# CH3-Input.net
KiCad netlist of a schematic drawn in Altium Designer
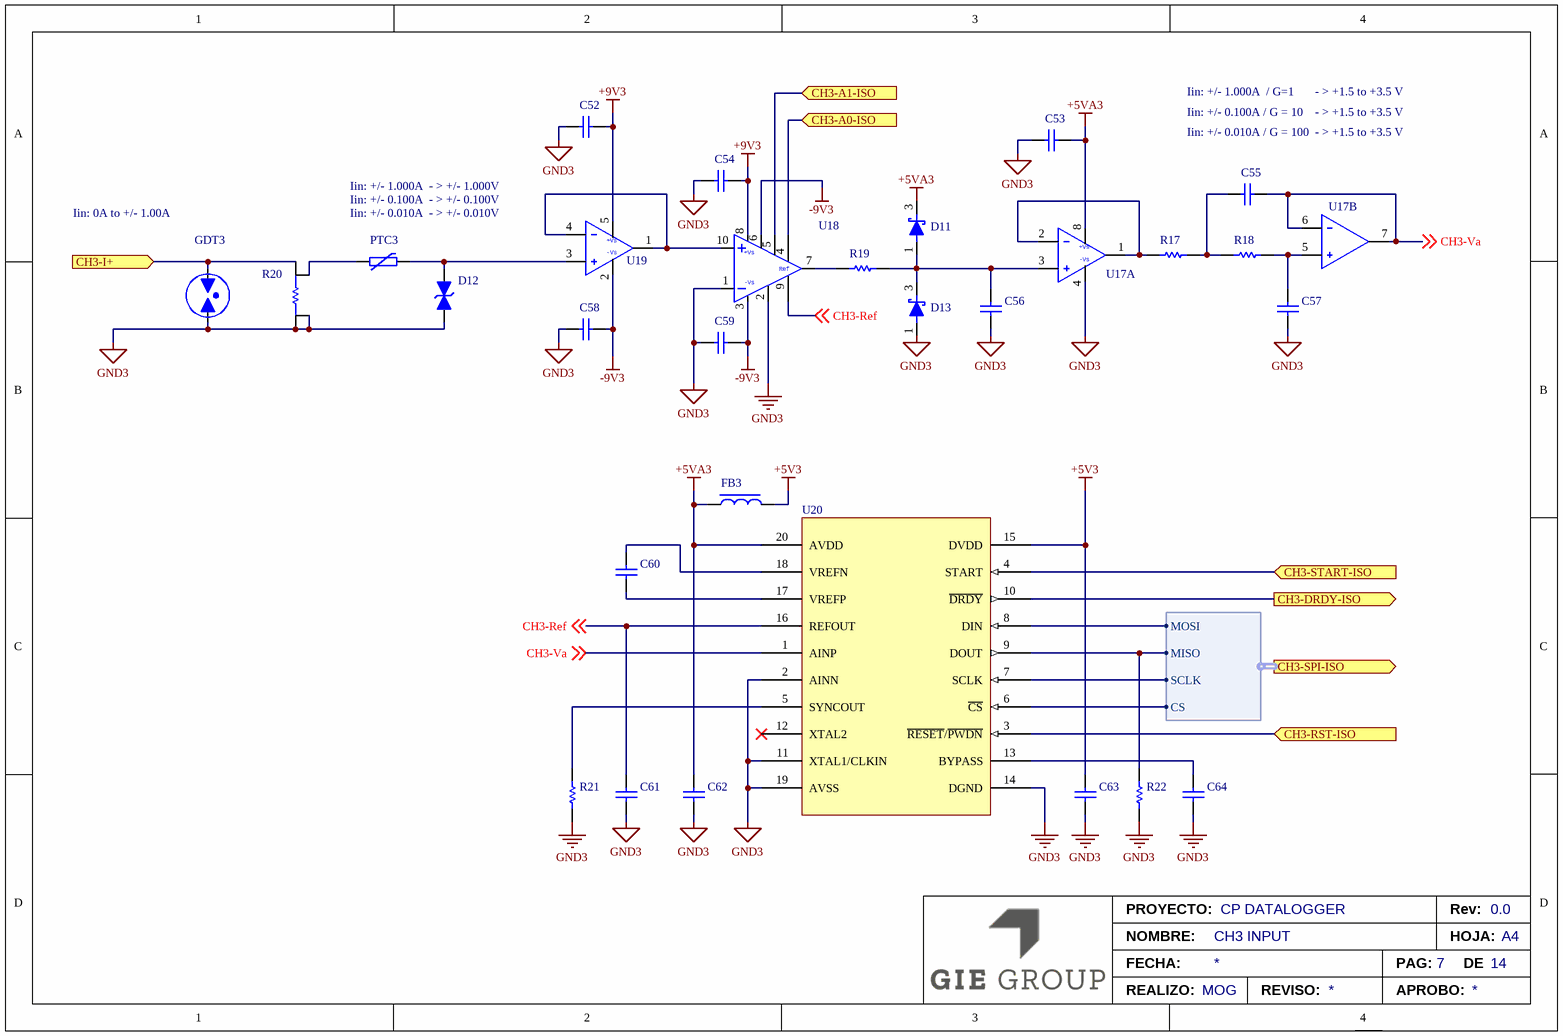
[diagram p0: CH3-Input.SchDoc]

(export (version "E")
  (design (tool "Eeschema 10.0.6"))
  (components
    (comp (ref "C52")
      (value "C0603C104K5RACAUTO")
      (footprint "CAP-0603")
      (description "CAP CER 0.1uF 50V X7R 0603")
      (fields (field (name "MANUFACTURER") "Kemet") (field (name "TOLERANCE") "10%"))
      (libsource (lib "Kemet") (part "C0603C104K5RACAUTO"))
    )
    (comp (ref "C53")
      (value "C0603C104K5RACAUTO")
      (footprint "CAP-0603")
      (description "CAP CER 0.1uF 50V X7R 0603")
      (fields (field (name "MANUFACTURER") "Kemet") (field (name "TOLERANCE") "10%"))
      (libsource (lib "Kemet") (part "C0603C104K5RACAUTO"))
    )
    (comp (ref "C54")
      (value "C0603C104K5RACAUTO")
      (footprint "CAP-0603")
      (description "CAP CER 0.1uF 50V X7R 0603")
      (fields (field (name "MANUFACTURER") "Kemet") (field (name "TOLERANCE") "10%"))
      (libsource (lib "Kemet") (part "C0603C104K5RACAUTO"))
    )
    (comp (ref "C55")
      (value "C0603C162J5GAC7867")
      (footprint "CAP-0603")
      (description "CAP CER 1600´pF 50V C0G 0603")
      (fields (field (name "MANUFACTURER") "Kemet") (field (name "TOLERANCE") "5%"))
      (libsource (lib "Kemet") (part "C0603C162J5GAC7867"))
    )
    (comp (ref "C56")
      (value "C0603C162J5GAC7867")
      (footprint "CAP-0603")
      (description "CAP CER 1600´pF 50V C0G 0603")
      (fields (field (name "MANUFACTURER") "Kemet") (field (name "TOLERANCE") "5%"))
      (libsource (lib "Kemet") (part "C0603C162J5GAC7867"))
    )
    (comp (ref "C57")
      (value "C0603C161J1GAC7867")
      (footprint "CAP-0603")
      (description "CAP CER 160 pF 100V C0G 0603")
      (fields (field (name "MANUFACTURER") "Kemet") (field (name "TOLERANCE") "5%"))
      (libsource (lib "Kemet") (part "C0603C161J1GAC7867"))
    )
    (comp (ref "C58")
      (value "C0603C104K5RACAUTO")
      (footprint "CAP-0603")
      (description "CAP CER 0.1uF 50V X7R 0603")
      (fields (field (name "MANUFACTURER") "Kemet") (field (name "TOLERANCE") "10%"))
      (libsource (lib "Kemet") (part "C0603C104K5RACAUTO"))
    )
    (comp (ref "C59")
      (value "C0603C104K5RACAUTO")
      (footprint "CAP-0603")
      (description "CAP CER 0.1uF 50V X7R 0603")
      (fields (field (name "MANUFACTURER") "Kemet") (field (name "TOLERANCE") "10%"))
      (libsource (lib "Kemet") (part "C0603C104K5RACAUTO"))
    )
    (comp (ref "C60")
      (value "C0603C105M3RAC7867")
      (footprint "CAP-0603")
      (description "CAP CER 1uF 25V X7R 0603")
      (fields (field (name "MANUFACTURER") "Kemet") (field (name "TOLERANCE") "20%"))
      (libsource (lib "Kemet") (part "C0603C105M3RAC7867"))
    )
    (comp (ref "C61")
      (value "C0603C105M3RAC7867")
      (footprint "CAP-0603")
      (description "CAP CER 1uF 25V X7R 0603")
      (fields (field (name "MANUFACTURER") "Kemet") (field (name "TOLERANCE") "20%"))
      (libsource (lib "Kemet") (part "C0603C105M3RAC7867"))
    )
    (comp (ref "C62")
      (value "C0603C105M3RAC7867")
      (footprint "CAP-0603")
      (description "CAP CER 1uF 25V X7R 0603")
      (fields (field (name "MANUFACTURER") "Kemet") (field (name "TOLERANCE") "20%"))
      (libsource (lib "Kemet") (part "C0603C105M3RAC7867"))
    )
    (comp (ref "C63")
      (value "C0603C105M3RAC7867")
      (footprint "CAP-0603")
      (description "CAP CER 1uF 25V X7R 0603")
      (fields (field (name "MANUFACTURER") "Kemet") (field (name "TOLERANCE") "20%"))
      (libsource (lib "Kemet") (part "C0603C105M3RAC7867"))
    )
    (comp (ref "C64")
      (value "C0603C105M3RAC7867")
      (footprint "CAP-0603")
      (description "CAP CER 1uF 25V X7R 0603")
      (fields (field (name "MANUFACTURER") "Kemet") (field (name "TOLERANCE") "20%"))
      (libsource (lib "Kemet") (part "C0603C105M3RAC7867"))
    )
    (comp (ref "D11")
      (value "NSVBAT54WT1G")
      (footprint "SOT-323-3")
      (description "Schottky Diode 30V 200mA SOT323")
      (fields (field (name "MANUFACTURER") "OnSemiconductor"))
      (libsource (lib "OnSemiconductors") (part "NSVBAT54WT1G"))
    )
    (comp (ref "D12")
      (value "~")
      (footprint "DIODE-0603")
      (description "TVS Diode 1.5kW 130V 5% Bi-Directional")
      (fields (field (name "MANUFACTURER") "Diodes Inc"))
      (libsource (lib "DidesInc") (part "D3V3L1B2LP3-7"))
    )
    (comp (ref "D13")
      (value "~")
      (footprint "SOT-323-3")
      (description "Schottky Diode 30V 200mA SOT323")
      (fields (field (name "MANUFACTURER") "OnSemiconductor"))
      (libsource (lib "OnSemiconductors") (part "NSVBAT54WT1G"))
    )
    (comp (ref "FB3")
      (value "Z0603C121GPWZT")
      (footprint "IND-0603")
      (description "Ferrite Bead 120Ohms 900mA 25% DCR=130m")
      (fields (field (name "MANUFACTURER") "Kemet"))
      (libsource (lib "Kemet") (part "Z0603C121GPWZT"))
    )
    (comp (ref "GDT3")
      (value "~")
      (footprint "LITTLELFUSE-CG5XXXLTR")
      (description "Gas Discharge Tube 145V")
      (fields (field (name "MANUFACTURER") "Littelfuse"))
      (libsource (lib "Littlelfuse") (part "CG5145LTR"))
    )
    (comp (ref "PTC3")
      (value "~")
      (footprint "LITTLELFUSE-72R020X")
      (description "PTC Polyfuse Radial 72V 0.2A")
      (fields (field (name "MANUFACTURER") "Littlelfuse"))
      (libsource (lib "Littlelfuse") (part "72R020XPR"))
    )
    (comp (ref "R17")
      (value "RC0603FR-07113KL")
      (footprint "RES-0603")
      (description "RES SMD 113K OHM 1% 1/10W 0603")
      (fields (field (name "TOLERANCE") "1%") (field (name "MANUFACTURER") "Yageo"))
      (libsource (lib "Yageo") (part "RC0603FR-07113KL"))
    )
    (comp (ref "R18")
      (value "RC0603FR-07887KL")
      (footprint "RES-0603")
      (description "RES SMD 887K OHM 1% 1/10W 0603")
      (fields (field (name "TOLERANCE") "1%") (field (name "MANUFACTURER") "Yageo"))
      (libsource (lib "Yageo") (part "RC0603FR-07887KL"))
    )
    (comp (ref "R19")
      (value "RC0603FR-07100KL")
      (footprint "RES-0603")
      (description "RES SMD 100K OHM 1% 1/10W 0603")
      (fields (field (name "TOLERANCE") "1%") (field (name "MANUFACTURER") "Yageo"))
      (libsource (lib "Yageo") (part "RC0603FR-07100KL"))
    )
    (comp (ref "R20")
      (value "Y16061R00000B9W")
      (footprint "RES-2512 WIDE")
      (description "RES SMD 1 OHM 1W 2516 WIDE")
      (fields (field (name "MANUFACTURER") "Vishay"))
      (libsource (lib "Vishay") (part "Y16061R00000B9W"))
    )
    (comp (ref "R21")
      (value "RC0603FR-071ML")
      (footprint "RES-0603")
      (description "RES SMD 1M OHM 1% 1/10W 0603")
      (fields (field (name "TOLERANCE") "1%") (field (name "MANUFACTURER") "Yageo"))
      (libsource (lib "Yageo") (part "RC0603FR-071ML"))
    )
    (comp (ref "R22")
      (value "RC0603FR-071ML")
      (footprint "RES-0603")
      (description "RES SMD 1M OHM 1% 1/10W 0603")
      (fields (field (name "TOLERANCE") "1%") (field (name "MANUFACTURER") "Yageo"))
      (libsource (lib "Yageo") (part "RC0603FR-071ML"))
    )
    (comp (ref "U17")
      (value "~")
      (footprint "MSOP8")
      (description "Dual  Precision Amplifier Micro Power Auto Zero")
      (fields (field (name "MANUFACTURER") "Analog Devices"))
      (libsource (lib "AnalogDevices") (part "ADA4051-2ARMZ"))
    )
    (comp (ref "U18")
      (value "AD8253ARMZ")
      (footprint "MSOP10")
      (description "Instrumentation Amplifiers High Speed Programmable High Gain In-Amp")
      (fields (field (name "MANUFACTURER") "Analog Devices Inc"))
      (libsource (lib "AnalogDevices") (part "AD8253ARMZ"))
    )
    (comp (ref "U19")
      (value "~")
      (footprint "SOT23-5")
      (description "16V Auto-Zero CMOS Amplifier")
      (fields (field (name "MANUFACTURER") "Analog Devices"))
      (libsource (lib "AnalogDevices") (part "AD8638ARJZ"))
    )
    (comp (ref "U20")
      (value "~")
      (footprint "TSSOP20")
      (description "Analog to Digital Converter 14.4kSPS 24-Bit")
      (fields (field (name "MANUFACTURER") "Texas Instruments"))
      (libsource (lib "TexasInstruments") (part "ADS1259BIPW"))
    )
  )
  (nets
    (net (code "2") (name "+5V3") (class "Default")
      (node (ref "C63") (pin "2") (pinfunction "2_2") (pintype "passive"))
      (node (ref "FB3") (pin "2") (pinfunction "2_2") (pintype "passive"))
      (node (ref "U20") (pin "15") (pinfunction "DVDD_15") (pintype "power_in"))
    )
    (net (code "3") (name "+5VA3") (class "Default")
      (node (ref "C53") (pin "2") (pinfunction "2_2") (pintype "passive"))
      (node (ref "C62") (pin "2") (pinfunction "2_2") (pintype "passive"))
      (node (ref "D11") (pin "3") (pinfunction "K_3") (pintype "passive"))
      (node (ref "FB3") (pin "1") (pinfunction "1_1") (pintype "passive"))
      (node (ref "U17") (pin "8") (pinfunction "+VS_8") (pintype "power_in"))
      (node (ref "U20") (pin "20") (pinfunction "AVDD_20") (pintype "power_in"))
    )
    (net (code "4") (name "+9V3") (class "Default")
      (node (ref "C52") (pin "2") (pinfunction "2_2") (pintype "passive"))
      (node (ref "C54") (pin "2") (pinfunction "2_2") (pintype "passive"))
      (node (ref "U18") (pin "8") (pinfunction "+Vs_8") (pintype "passive"))
      (node (ref "U19") (pin "5") (pinfunction "+VS_5") (pintype "power_in"))
    )
    (net (code "5") (name "-9V3") (class "Default")
      (node (ref "C58") (pin "2") (pinfunction "2_2") (pintype "passive"))
      (node (ref "C59") (pin "2") (pinfunction "2_2") (pintype "passive"))
      (node (ref "U18") (pin "3") (pinfunction "-Vs_3") (pintype "passive"))
      (node (ref "U18") (pin "6") (pinfunction "WR_6") (pintype "passive"))
      (node (ref "U19") (pin "2") (pinfunction "-Vs_2") (pintype "power_in"))
    )
    (net (code "6") (name "/CH3-A0-ISO") (class "Default")
      (node (ref "U18") (pin "4") (pinfunction "A0_4") (pintype "passive"))
    )
    (net (code "7") (name "/CH3-A1-ISO") (class "Default")
      (node (ref "U18") (pin "5") (pinfunction "A1_5") (pintype "passive"))
    )
    (net (code "8") (name "/CH3-DRDY-ISO") (class "Default")
      (node (ref "U20") (pin "10") (pinfunction "~{DRDY}_10") (pintype "output"))
    )
    (net (code "9") (name "/CH3-I+") (class "Default")
      (node (ref "GDT3") (pin "1") (pinfunction "A_1") (pintype "passive"))
      (node (ref "R20") (pin "I1") (pinfunction "1_I1") (pintype "passive"))
    )
    (net (code "10") (name "/CH3-RST-ISO") (class "Default")
      (node (ref "U20") (pin "3") (pinfunction "~{RESET}/~{PWDN}_3") (pintype "input"))
    )
    (net (code "11") (name "/CH3-START-ISO") (class "Default")
      (node (ref "U20") (pin "4") (pinfunction "START_4") (pintype "input"))
    )
    (net (code "12") (name "/CS") (class "Default")
      (node (ref "U20") (pin "6") (pinfunction "~{CS}_6") (pintype "input"))
    )
    (net (code "13") (name "/MISO") (class "Default")
      (node (ref "R22") (pin "2") (pinfunction "2_2") (pintype "passive"))
      (node (ref "U20") (pin "9") (pinfunction "DOUT_9") (pintype "output"))
    )
    (net (code "14") (name "/MOSI") (class "Default")
      (node (ref "U20") (pin "8") (pinfunction "DIN_8") (pintype "input"))
    )
    (net (code "15") (name "/SCLK") (class "Default")
      (node (ref "U20") (pin "7") (pinfunction "SCLK_7") (pintype "input"))
    )
    (net (code "17") (name "CH3-Ref") (class "Default")
      (node (ref "C61") (pin "2") (pinfunction "2_2") (pintype "passive"))
      (node (ref "U18") (pin "9") (pinfunction "REF_9") (pintype "passive"))
      (node (ref "U20") (pin "16") (pinfunction "REFOUT_16") (pintype "power_in"))
    )
    (net (code "18") (name "CH3-Va") (class "Default")
      (node (ref "C55") (pin "1") (pinfunction "1_1") (pintype "passive"))
      (node (ref "U17") (pin "6") (pinfunction "-INB_6") (pintype "passive"))
      (node (ref "U17") (pin "7") (pinfunction "OUTB_7") (pintype "passive"))
      (node (ref "U20") (pin "1") (pinfunction "AINP_1") (pintype "passive"))
    )
    (net (code "19") (name "GND3") (class "Default")
      (node (ref "C52") (pin "1") (pinfunction "1_1") (pintype "passive"))
      (node (ref "C53") (pin "1") (pinfunction "1_1") (pintype "passive"))
      (node (ref "C54") (pin "1") (pinfunction "1_1") (pintype "passive"))
      (node (ref "C56") (pin "1") (pinfunction "1_1") (pintype "passive"))
      (node (ref "C57") (pin "1") (pinfunction "1_1") (pintype "passive"))
      (node (ref "C58") (pin "1") (pinfunction "1_1") (pintype "passive"))
      (node (ref "C59") (pin "1") (pinfunction "1_1") (pintype "passive"))
      (node (ref "C61") (pin "1") (pinfunction "1_1") (pintype "passive"))
      (node (ref "C62") (pin "1") (pinfunction "1_1") (pintype "passive"))
      (node (ref "C63") (pin "1") (pinfunction "1_1") (pintype "passive"))
      (node (ref "C64") (pin "1") (pinfunction "1_1") (pintype "passive"))
      (node (ref "D12") (pin "2") (pinfunction "K_2") (pintype "passive"))
      (node (ref "D13") (pin "1") (pinfunction "A_1") (pintype "passive"))
      (node (ref "GDT3") (pin "2") (pinfunction "K_2") (pintype "passive"))
      (node (ref "R20") (pin "E2") (pinfunction "1_E2") (pintype "passive"))
      (node (ref "R20") (pin "I2") (pinfunction "2_I2") (pintype "passive"))
      (node (ref "R21") (pin "1") (pinfunction "1_1") (pintype "passive"))
      (node (ref "R22") (pin "1") (pinfunction "1_1") (pintype "passive"))
      (node (ref "U17") (pin "4") (pinfunction "-Vs_4") (pintype "power_in"))
      (node (ref "U18") (pin "1") (pinfunction "-_IN_1") (pintype "passive"))
      (node (ref "U18") (pin "2") (pinfunction "DGND_2") (pintype "passive"))
      (node (ref "U20") (pin "11") (pinfunction "XTAL1/CLKIN_11") (pintype "power_in"))
      (node (ref "U20") (pin "14") (pinfunction "DGND_14") (pintype "power_in"))
      (node (ref "U20") (pin "19") (pinfunction "AVSS_19") (pintype "power_in"))
      (node (ref "U20") (pin "2") (pinfunction "AINN_2") (pintype "passive"))
    )
    (net (code "20") (name "Net-(C55-Pad2)") (class "Default")
      (node (ref "C55") (pin "2") (pinfunction "2_2") (pintype "passive"))
      (node (ref "R17") (pin "2") (pinfunction "2_2") (pintype "passive"))
      (node (ref "R18") (pin "1") (pinfunction "1_1") (pintype "passive"))
    )
    (net (code "21") (name "Net-(D11-A)") (class "Default")
      (node (ref "C56") (pin "2") (pinfunction "2_2") (pintype "passive"))
      (node (ref "D11") (pin "1") (pinfunction "A_1") (pintype "passive"))
      (node (ref "D13") (pin "3") (pinfunction "K_3") (pintype "passive"))
      (node (ref "R19") (pin "2") (pinfunction "2_2") (pintype "passive"))
      (node (ref "U17") (pin "3") (pinfunction "+INA_3") (pintype "passive"))
    )
    (net (code "22") (name "Net-(D12-A)") (class "Default")
      (node (ref "D12") (pin "1") (pinfunction "A_1") (pintype "passive"))
      (node (ref "PTC3") (pin "2") (pinfunction "2_2") (pintype "passive"))
      (node (ref "U19") (pin "3") (pinfunction "+IN_3") (pintype "passive"))
    )
    (net (code "23") (name "Net-(PTC3-Pad1)") (class "Default")
      (node (ref "PTC3") (pin "1") (pinfunction "1_1") (pintype "passive"))
      (node (ref "R20") (pin "E1") (pinfunction "1_E1") (pintype "passive"))
    )
    (net (code "24") (name "Net-(U17A--INA)") (class "Default")
      (node (ref "R17") (pin "1") (pinfunction "1_1") (pintype "passive"))
      (node (ref "U17") (pin "1") (pinfunction "OUTA_1") (pintype "passive"))
      (node (ref "U17") (pin "2") (pinfunction "-INA_2") (pintype "passive"))
    )
    (net (code "25") (name "Net-(U17B-+INB)") (class "Default")
      (node (ref "C57") (pin "2") (pinfunction "2_2") (pintype "passive"))
      (node (ref "R18") (pin "2") (pinfunction "2_2") (pintype "passive"))
      (node (ref "U17") (pin "5") (pinfunction "+INB_5") (pintype "passive"))
    )
    (net (code "26") (name "Net-(U18-+_IN)") (class "Default")
      (node (ref "U18") (pin "10") (pinfunction "+_IN_10") (pintype "passive"))
      (node (ref "U19") (pin "1") (pinfunction "OUT_1") (pintype "passive"))
      (node (ref "U19") (pin "4") (pinfunction "-IN_4") (pintype "passive"))
    )
    (net (code "27") (name "Net-(U18-OUT)") (class "Default")
      (node (ref "R19") (pin "1") (pinfunction "1_1") (pintype "passive"))
      (node (ref "U18") (pin "7") (pinfunction "OUT_7") (pintype "passive"))
    )
    (net (code "28") (name "Net-(U20-BYPASS)") (class "Default")
      (node (ref "C64") (pin "2") (pinfunction "2_2") (pintype "passive"))
      (node (ref "U20") (pin "13") (pinfunction "BYPASS_13") (pintype "power_in"))
    )
    (net (code "29") (name "Net-(U20-SYNCOUT)") (class "Default")
      (node (ref "R21") (pin "2") (pinfunction "2_2") (pintype "passive"))
      (node (ref "U20") (pin "5") (pinfunction "SYNCOUT_5") (pintype "passive"))
    )
    (net (code "30") (name "Net-(U20-VREFN)") (class "Default")
      (node (ref "C60") (pin "2") (pinfunction "2_2") (pintype "passive"))
      (node (ref "U20") (pin "18") (pinfunction "VREFN_18") (pintype "power_in"))
    )
    (net (code "31") (name "Net-(U20-VREFP)") (class "Default")
      (node (ref "C60") (pin "1") (pinfunction "1_1") (pintype "passive"))
      (node (ref "U20") (pin "17") (pinfunction "VREFP_17") (pintype "power_in"))
    )
    (net (code "32") (name "unconnected-(U20-XTAL2-Pad12)") (class "Default")
      (node (ref "U20") (pin "12") (pinfunction "XTAL2_12") (pintype "power_in+no_connect"))
    )
  )
)
